# RTC.net
KiCad netlist of a schematic drawn in Altium Designer
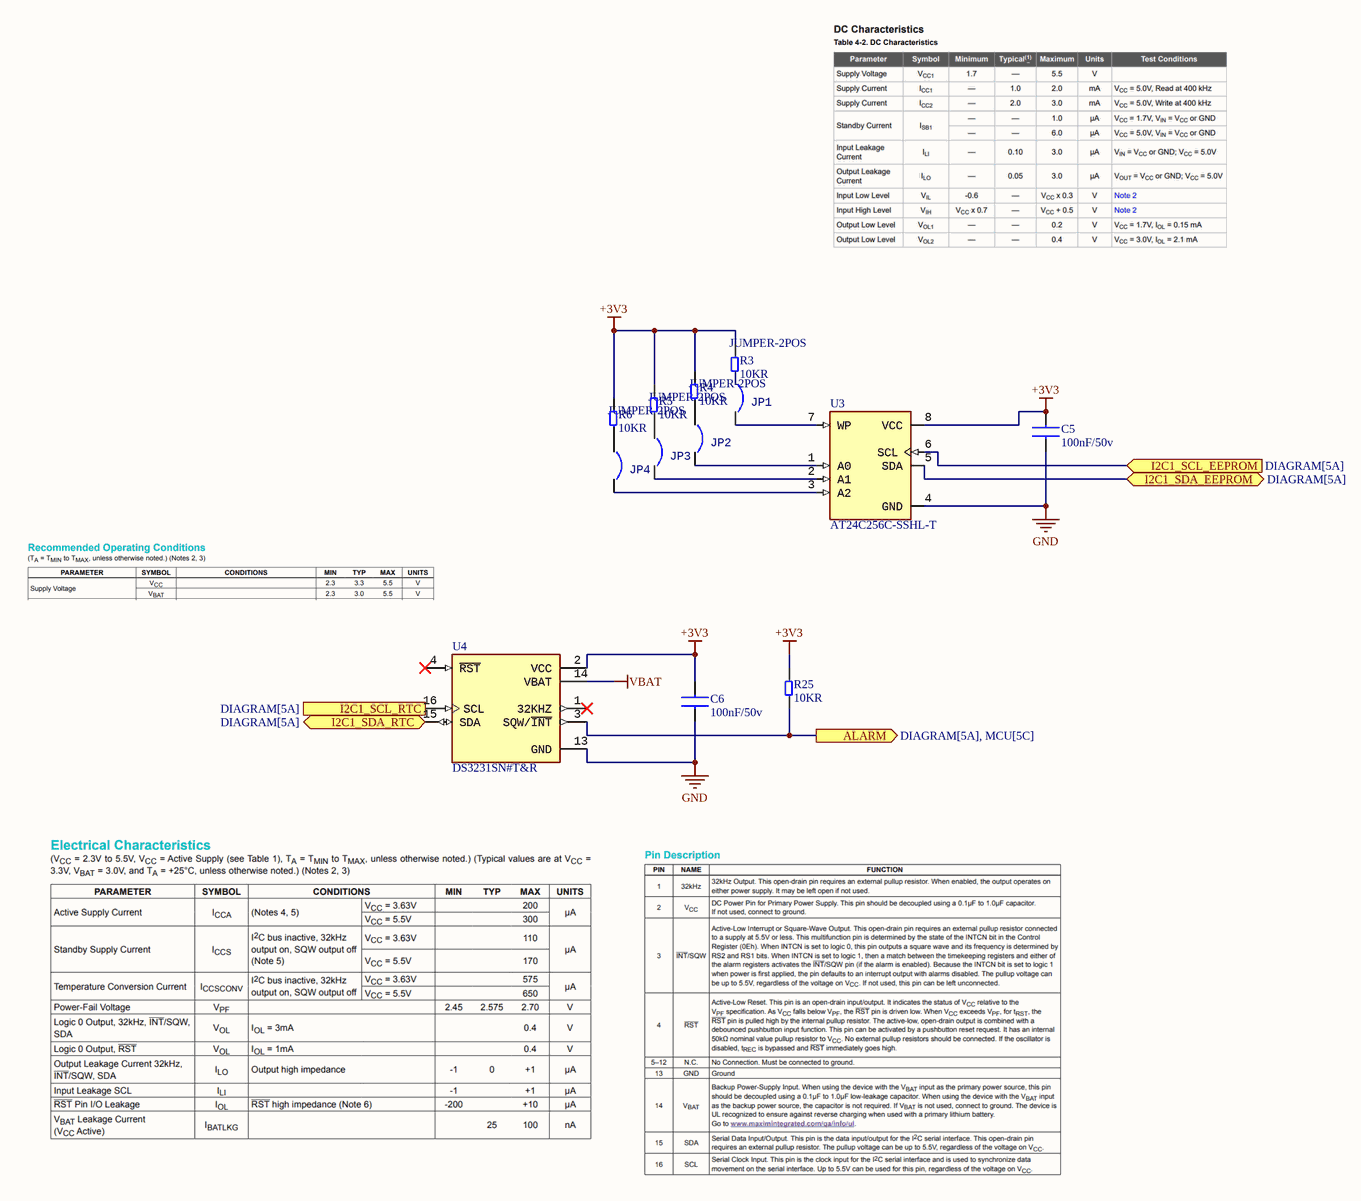
[diagram p0: RTC.SchDoc]

(export (version "E")
  (design (tool "Eeschema 10.0.6"))
  (components
    (comp (ref "C5") (value "100nF/50v") (footprint "CAP-CER-0805") (libsource (lib "ID") (part "CAP-CER")))
    (comp (ref "C6") (value "100nF/50v") (footprint "CAP-CER-0805") (libsource (lib "ID") (part "CAP-CER")))
    (comp (ref "JP1")
      (value "JUMPER-2POS")
      (footprint "JUMPER-2POS-2.54")
      (fields (field (name "MFR# #") "JUMPER-2POS"))
      (libsource (lib "Database_Libs1") (part "JUMPER-2POS"))
    )
    (comp (ref "JP2")
      (value "JUMPER-2POS")
      (footprint "JUMPER-2POS-2.54")
      (fields (field (name "MFR# #") "JUMPER-2POS"))
      (libsource (lib "Database_Libs1") (part "JUMPER-2POS"))
    )
    (comp (ref "JP3")
      (value "JUMPER-2POS")
      (footprint "JUMPER-2POS-2.54")
      (fields (field (name "MFR# #") "JUMPER-2POS"))
      (libsource (lib "Database_Libs1") (part "JUMPER-2POS"))
    )
    (comp (ref "JP4")
      (value "JUMPER-2POS")
      (footprint "JUMPER-2POS-2.54")
      (fields (field (name "MFR# #") "JUMPER-2POS"))
      (libsource (lib "Database_Libs1") (part "JUMPER-2POS"))
    )
    (comp (ref "R3") (value "10KR") (footprint "RES-SMD-0805") (libsource (lib "ID") (part "RES_SMD")))
    (comp (ref "R4") (value "10KR") (footprint "RES-SMD-0805") (libsource (lib "ID") (part "RES_SMD")))
    (comp (ref "R5") (value "10KR") (footprint "RES-SMD-0805") (libsource (lib "ID") (part "RES_SMD")))
    (comp (ref "R6") (value "10KR") (footprint "RES-SMD-0805") (libsource (lib "ID") (part "RES_SMD")))
    (comp (ref "R25") (value "10KR") (footprint "RES-SMD-0805") (libsource (lib "ID") (part "RES_SMD")))
    (comp (ref "U3")
      (value "AT24C256C-SSHL-T")
      (footprint "AT24C256C-SSHL-T")
      (description "EEPROM Memory IC 256Kbit I2C 1 MHz 550 ns 8-SOIC")
      (fields (field (name "MFR# #") "AT24C256C-SSHL-T"))
      (libsource (lib "Database_Libs1") (part "AT24C256C"))
    )
    (comp (ref "U4")
      (value "DS3231SN#T&R")
      (footprint "DS3231SN_SOIC127P1032X265-16N")
      (description "Real Time Clock (RTC) IC Clock/Calendar I2C, 2-Wire Serial 16-SOIC (0.295\", 7.50mm Width)")
      (fields (field (name "MFR# #") "DS3231SN#T&R"))
      (libsource (lib "Database_Libs1") (part "DS3231SN"))
    )
  )
  (nets
    (net (code "1") (name "+3V3") (class "Default")
      (node (ref "C5") (pin "2") (pinfunction "2_2") (pintype "passive"))
      (node (ref "C6") (pin "2") (pinfunction "2_2") (pintype "passive"))
      (node (ref "R25") (pin "2") (pinfunction "2_2") (pintype "passive"))
      (node (ref "R3") (pin "2") (pinfunction "2_2") (pintype "passive"))
      (node (ref "R4") (pin "2") (pinfunction "2_2") (pintype "passive"))
      (node (ref "R5") (pin "2") (pinfunction "2_2") (pintype "passive"))
      (node (ref "R6") (pin "2") (pinfunction "2_2") (pintype "passive"))
      (node (ref "U3") (pin "8") (pinfunction "VCC_8") (pintype "power_in"))
      (node (ref "U4") (pin "2") (pinfunction "VCC_2") (pintype "power_in"))
    )
    (net (code "2") (name "/ALARM") (class "Default")
      (node (ref "R25") (pin "1") (pinfunction "1_1") (pintype "passive"))
      (node (ref "U4") (pin "3") (pinfunction "SQW/~{INT}_3") (pintype "output"))
    )
    (net (code "3") (name "/I2C1_SCL_EEPROM") (class "Default")
      (node (ref "U3") (pin "6") (pinfunction "SCL_6") (pintype "input"))
    )
    (net (code "4") (name "/I2C1_SCL_RTC") (class "Default")
      (node (ref "U4") (pin "16") (pinfunction "SCL_16") (pintype "input"))
    )
    (net (code "5") (name "/I2C1_SDA_EEPROM") (class "Default")
      (node (ref "U3") (pin "5") (pinfunction "SDA_5") (pintype "bidirectional"))
    )
    (net (code "6") (name "/I2C1_SDA_RTC") (class "Default")
      (node (ref "U4") (pin "15") (pinfunction "SDA_15") (pintype "bidirectional"))
    )
    (net (code "7") (name "GND") (class "Default")
      (node (ref "C5") (pin "1") (pinfunction "1_1") (pintype "passive"))
      (node (ref "C6") (pin "1") (pinfunction "1_1") (pintype "passive"))
      (node (ref "U3") (pin "4") (pinfunction "GND_4") (pintype "power_in"))
      (node (ref "U4") (pin "13") (pinfunction "GND_13") (pintype "power_in"))
    )
    (net (code "8") (name "Net-(JP1-Pad1)") (class "Default")
      (node (ref "JP1") (pin "1") (pinfunction "1_1") (pintype "passive"))
      (node (ref "R3") (pin "1") (pinfunction "1_1") (pintype "passive"))
    )
    (net (code "9") (name "Net-(JP2-Pad1)") (class "Default")
      (node (ref "JP2") (pin "1") (pinfunction "1_1") (pintype "passive"))
      (node (ref "R4") (pin "1") (pinfunction "1_1") (pintype "passive"))
    )
    (net (code "10") (name "Net-(JP3-Pad1)") (class "Default")
      (node (ref "JP3") (pin "1") (pinfunction "1_1") (pintype "passive"))
      (node (ref "R5") (pin "1") (pinfunction "1_1") (pintype "passive"))
    )
    (net (code "11") (name "Net-(JP4-Pad1)") (class "Default")
      (node (ref "JP4") (pin "1") (pinfunction "1_1") (pintype "passive"))
      (node (ref "R6") (pin "1") (pinfunction "1_1") (pintype "passive"))
    )
    (net (code "12") (name "Net-(U3-A0)") (class "Default")
      (node (ref "JP2") (pin "2") (pinfunction "2_2") (pintype "passive"))
      (node (ref "U3") (pin "1") (pinfunction "A0_1") (pintype "input"))
    )
    (net (code "13") (name "Net-(U3-A1)") (class "Default")
      (node (ref "JP3") (pin "2") (pinfunction "2_2") (pintype "passive"))
      (node (ref "U3") (pin "2") (pinfunction "A1_2") (pintype "input"))
    )
    (net (code "14") (name "Net-(U3-A2)") (class "Default")
      (node (ref "JP4") (pin "2") (pinfunction "2_2") (pintype "passive"))
      (node (ref "U3") (pin "3") (pinfunction "A2_3") (pintype "input"))
    )
    (net (code "15") (name "Net-(U3-WP)") (class "Default")
      (node (ref "JP1") (pin "2") (pinfunction "2_2") (pintype "passive"))
      (node (ref "U3") (pin "7") (pinfunction "WP_7") (pintype "input"))
    )
    (net (code "16") (name "VBAT") (class "Default")
      (node (ref "U4") (pin "14") (pinfunction "VBAT_14") (pintype "power_in"))
    )
    (net (code "17") (name "unconnected-(U4-32KHZ-Pad1)") (class "Default")
      (node (ref "U4") (pin "1") (pinfunction "32KHZ_1") (pintype "output+no_connect"))
    )
    (net (code "18") (name "unconnected-(U4-~{RST}-Pad4)") (class "Default")
      (node (ref "U4") (pin "4") (pinfunction "~{RST}_4") (pintype "input+no_connect"))
    )
  )
)
